# esp8266-programmer.net
KiCad netlist of a schematic drawn in EAGLE
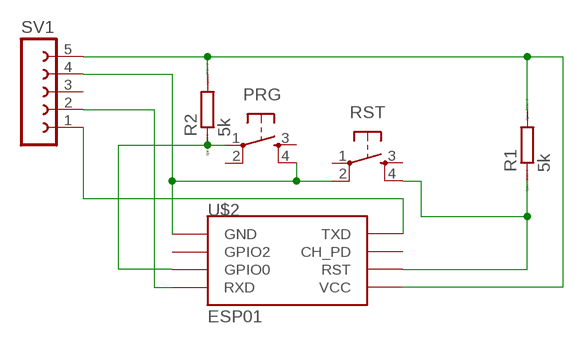
[diagram p0: schematic, sheet 1]

(export (version "E")
  (design (tool "Eeschema 10.0.6"))
  (components
    (comp (ref "PRG")
      (value "TAC_SWITCHPTH")
      (footprint "eagle-import:TACTILE-PTH")
      (libsource (lib "eagle-import") (part "TAC_SWITCHPTH"))
    )
    (comp (ref "R1")
      (value "5k")
      (footprint "eagle-import:0207_10")
      (libsource (lib "eagle-import") (part "R0207/10"))
    )
    (comp (ref "R2")
      (value "5k")
      (footprint "eagle-import:0207_10")
      (libsource (lib "eagle-import") (part "R0207/10"))
    )
    (comp (ref "RST")
      (value "TAC_SWITCHPTH")
      (footprint "eagle-import:TACTILE-PTH")
      (libsource (lib "eagle-import") (part "TAC_SWITCHPTH"))
    )
    (comp (ref "SV1")
      (value "FE05W")
      (footprint "eagle-import:FE05W")
      (libsource (lib "eagle-import") (part "FE05W"))
    )
    (comp (ref "U$2")
      (value "ESP01")
      (footprint "eagle-import:ESP01")
      (libsource (lib "eagle-import") (part "ESP01"))
    )
  )
  (nets
    (net (code "1") (name "Net-(PRG-Pad1)") (class "Default")
      (node (ref "PRG") (pin "1") (pinfunction "1_1") (pintype "passive"))
      (node (ref "R2") (pin "1") (pinfunction "1_1") (pintype "passive"))
      (node (ref "U$2") (pin "GPIO0") (pinfunction "GPIO0_GPIO0") (pintype "bidirectional"))
    )
    (net (code "2") (name "Net-(PRG-Pad4)") (class "Default")
      (node (ref "PRG") (pin "4") (pinfunction "4_4") (pintype "passive"))
      (node (ref "RST") (pin "2") (pinfunction "2_2") (pintype "passive"))
      (node (ref "SV1") (pin "4") (pinfunction "4_4") (pintype "passive"))
      (node (ref "U$2") (pin "GND") (pinfunction "GND_GND") (pintype "bidirectional"))
    )
    (net (code "3") (name "Net-(R1-Pad1)") (class "Default")
      (node (ref "R1") (pin "1") (pinfunction "1_1") (pintype "passive"))
      (node (ref "RST") (pin "4") (pinfunction "4_4") (pintype "passive"))
      (node (ref "U$2") (pin "RST") (pinfunction "RST_RST") (pintype "bidirectional"))
    )
    (net (code "4") (name "Net-(R1-Pad2)") (class "Default")
      (node (ref "R1") (pin "2") (pinfunction "2_2") (pintype "passive"))
      (node (ref "R2") (pin "2") (pinfunction "2_2") (pintype "passive"))
      (node (ref "SV1") (pin "5") (pinfunction "5_5") (pintype "passive"))
      (node (ref "U$2") (pin "VCC") (pinfunction "VCC_VCC") (pintype "bidirectional"))
    )
    (net (code "5") (name "Net-(U$2-RXD)") (class "Default")
      (node (ref "SV1") (pin "2") (pinfunction "2_2") (pintype "passive"))
      (node (ref "U$2") (pin "RX") (pinfunction "RXD_RX") (pintype "bidirectional"))
    )
    (net (code "6") (name "Net-(U$2-TXD)") (class "Default")
      (node (ref "SV1") (pin "1") (pinfunction "1_1") (pintype "passive"))
      (node (ref "U$2") (pin "TX") (pinfunction "TXD_TX") (pintype "bidirectional"))
    )
    (net (code "7") (name "unconnected-(PRG-Pad2)") (class "Default")
      (node (ref "PRG") (pin "2") (pinfunction "2_2") (pintype "passive"))
    )
    (net (code "8") (name "unconnected-(PRG-Pad3)") (class "Default")
      (node (ref "PRG") (pin "3") (pinfunction "3_3") (pintype "passive"))
    )
    (net (code "9") (name "unconnected-(RST-Pad1)") (class "Default")
      (node (ref "RST") (pin "1") (pinfunction "1_1") (pintype "passive"))
    )
    (net (code "10") (name "unconnected-(RST-Pad3)") (class "Default")
      (node (ref "RST") (pin "3") (pinfunction "3_3") (pintype "passive"))
    )
    (net (code "11") (name "unconnected-(SV1-Pad3)") (class "Default")
      (node (ref "SV1") (pin "3") (pinfunction "3_3") (pintype "passive"))
    )
    (net (code "12") (name "unconnected-(U$2-PadCH_PD)") (class "Default")
      (node (ref "U$2") (pin "CH_PD") (pinfunction "CH_PD_CH_PD") (pintype "bidirectional"))
    )
    (net (code "13") (name "unconnected-(U$2-PadGPIO2)") (class "Default")
      (node (ref "U$2") (pin "GPIO2") (pinfunction "GPIO2_GPIO2") (pintype "bidirectional"))
    )
  )
)
